# NeoCoreShield.net
KiCad netlist of a schematic drawn in EAGLE
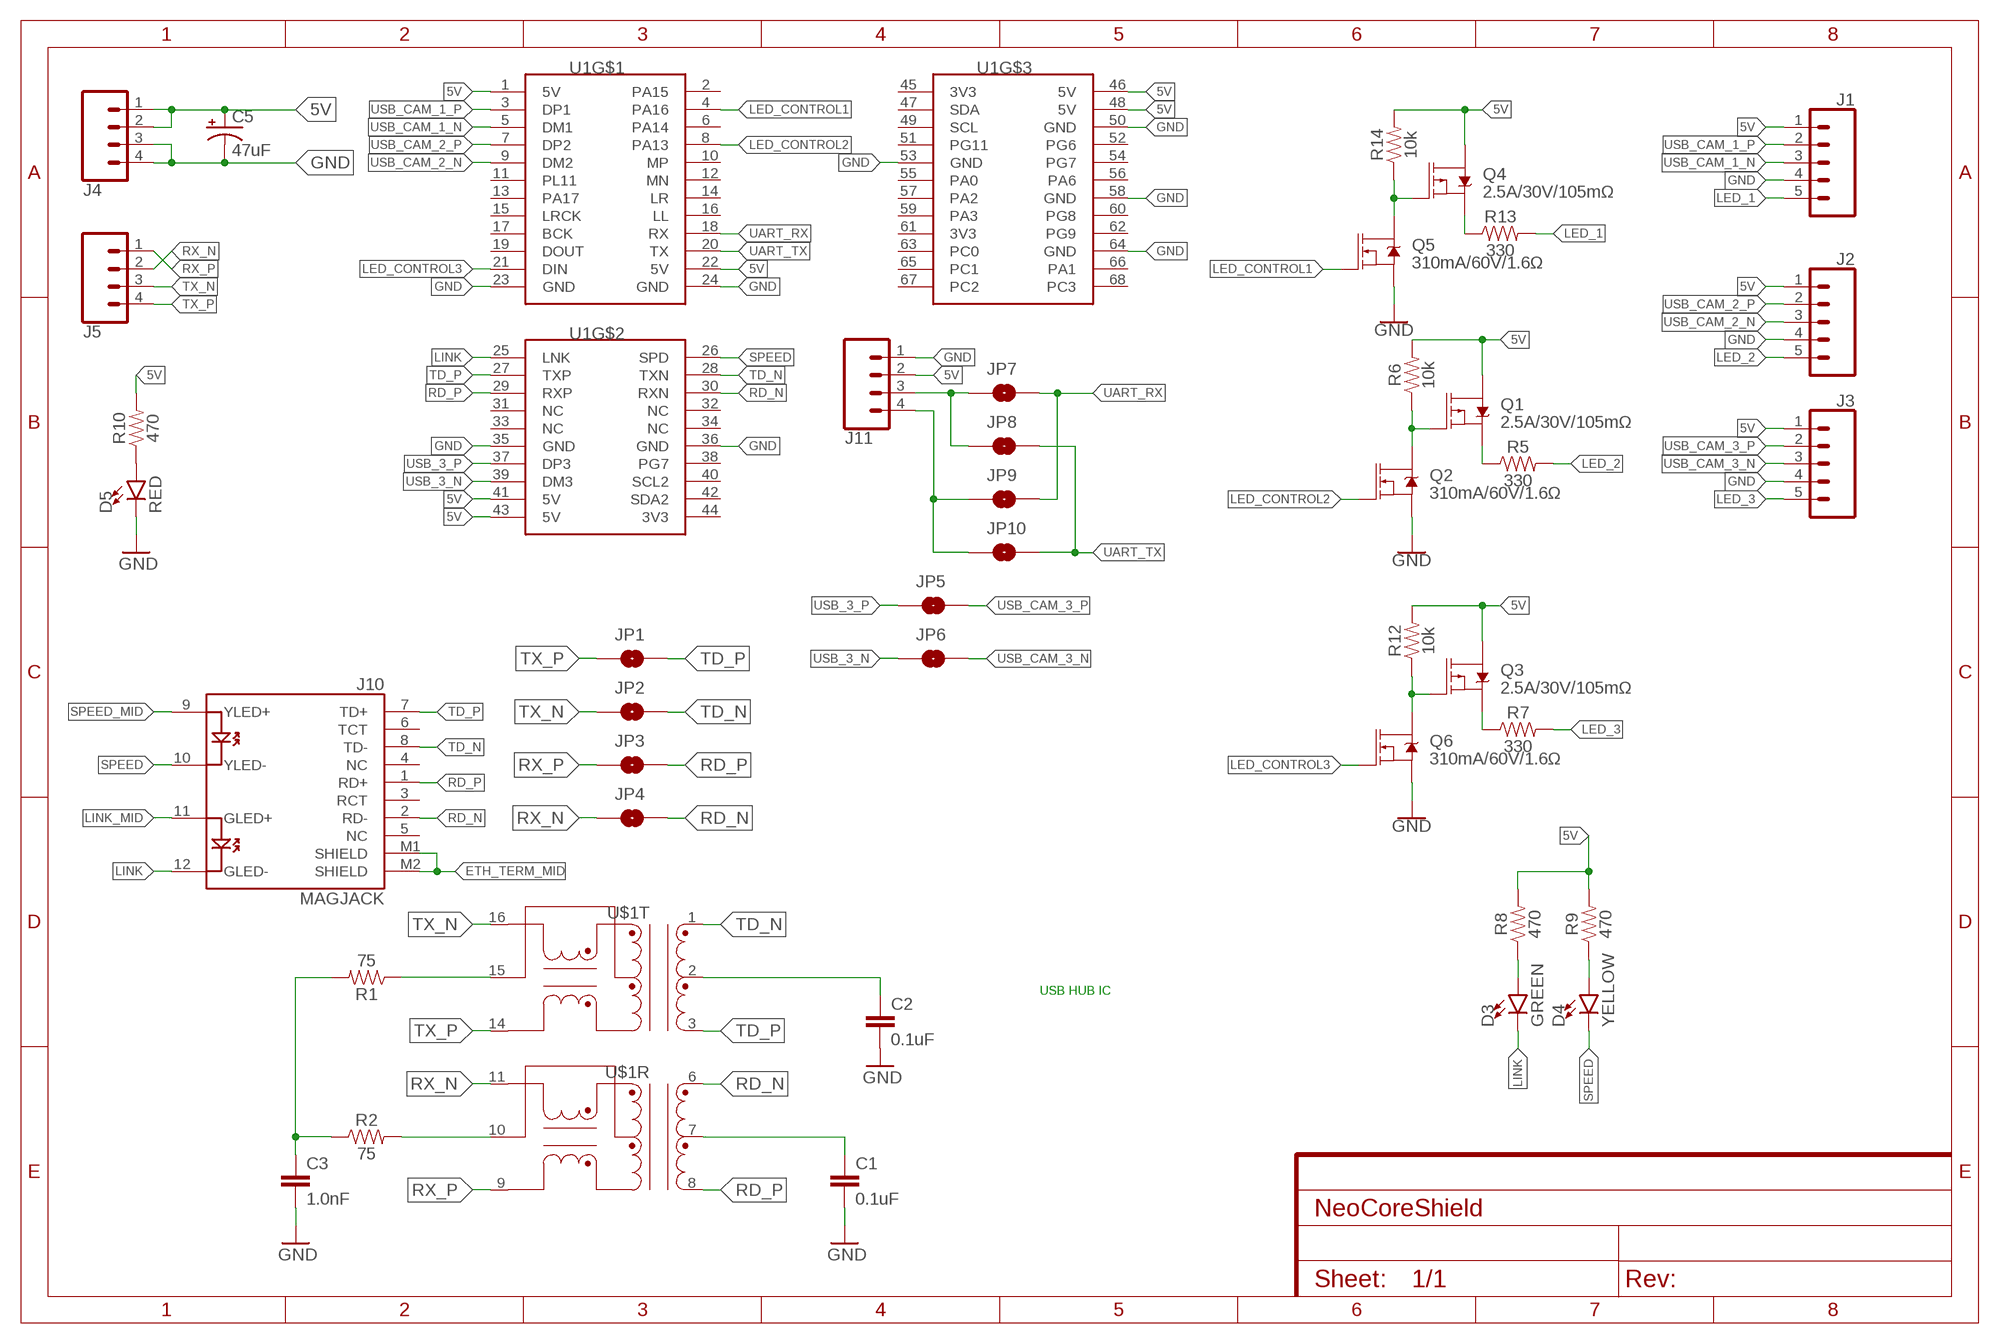
[diagram p0: schematic, sheet 1]

(export (version "E")
  (design (tool "Eeschema 10.0.6"))
  (components
    (comp (ref "C1")
      (value "0.1uF")
      (footprint "eagle-import:0603")
      (libsource (lib "eagle-import") (part "0.1UF-0603-25V-(+80/-20%)"))
    )
    (comp (ref "C2")
      (value "0.1uF")
      (footprint "eagle-import:0603")
      (libsource (lib "eagle-import") (part "0.1UF-0603-25V-(+80/-20%)"))
    )
    (comp (ref "C3")
      (value "1.0nF")
      (footprint "eagle-import:1206")
      (libsource (lib "eagle-import") (part "1.0UF-1206-50V-10%"))
    )
    (comp (ref "C5")
      (value "47uF")
      (footprint "eagle-import:PANASONIC_D")
      (libsource (lib "eagle-import") (part "47UF-POLAR-PANASONIC_D-35V-20%"))
    )
    (comp (ref "D3")
      (value "GREEN")
      (footprint "eagle-import:0805")
      (libsource (lib "eagle-import") (part "LED-0805"))
    )
    (comp (ref "D4")
      (value "YELLOW")
      (footprint "eagle-import:0805")
      (libsource (lib "eagle-import") (part "LED-0805"))
    )
    (comp (ref "D5")
      (value "RED")
      (footprint "eagle-import:0805")
      (libsource (lib "eagle-import") (part "LED-0805"))
    )
    (comp (ref "J1")
      (value "PXC-PTSM-05-RA")
      (footprint "eagle-import:PXC-PTSM-05-RA")
      (libsource (lib "eagle-import") (part "PXC-PTSM-05-RA"))
    )
    (comp (ref "J2")
      (value "PXC-PTSM-05-RA")
      (footprint "eagle-import:PXC-PTSM-05-RA")
      (libsource (lib "eagle-import") (part "PXC-PTSM-05-RA"))
    )
    (comp (ref "J3")
      (value "PXC-PTSM-05-RA")
      (footprint "eagle-import:PXC-PTSM-05-RA")
      (libsource (lib "eagle-import") (part "PXC-PTSM-05-RA"))
    )
    (comp (ref "J4")
      (value "PXC-PTSM-04-RA-1778641")
      (footprint "eagle-import:PXC-PTSM-04-RA-1778641")
      (libsource (lib "eagle-import") (part "PXC-PTSM-04-RA-1778641"))
    )
    (comp (ref "J5")
      (value "PXC-PTSM-04-RA-1778641")
      (footprint "eagle-import:PXC-PTSM-04-RA-1778641")
      (libsource (lib "eagle-import") (part "PXC-PTSM-04-RA-1778641"))
    )
    (comp (ref "J10")
      (value "MAGJACK")
      (footprint "eagle-import:MAGJACK")
      (libsource (lib "eagle-import") (part "MAGJACK"))
    )
    (comp (ref "J11")
      (value "CONN_04")
      (footprint "eagle-import:1X04")
      (libsource (lib "eagle-import") (part "CONN_04"))
    )
    (comp (ref "JP1")
      (value "JUMPER-SMT_2_NO_SILK")
      (footprint "eagle-import:SMT-JUMPER_2_NO_SILK")
      (libsource (lib "eagle-import") (part "JUMPER-SMT_2_NO_SILK"))
    )
    (comp (ref "JP2")
      (value "JUMPER-SMT_2_NO_SILK")
      (footprint "eagle-import:SMT-JUMPER_2_NO_SILK")
      (libsource (lib "eagle-import") (part "JUMPER-SMT_2_NO_SILK"))
    )
    (comp (ref "JP3")
      (value "JUMPER-SMT_2_NO_SILK")
      (footprint "eagle-import:SMT-JUMPER_2_NO_SILK")
      (libsource (lib "eagle-import") (part "JUMPER-SMT_2_NO_SILK"))
    )
    (comp (ref "JP4")
      (value "JUMPER-SMT_2_NO_SILK")
      (footprint "eagle-import:SMT-JUMPER_2_NO_SILK")
      (libsource (lib "eagle-import") (part "JUMPER-SMT_2_NO_SILK"))
    )
    (comp (ref "JP5")
      (value "JUMPER-SMT_2_NO_SILK")
      (footprint "eagle-import:SMT-JUMPER_2_NO_SILK")
      (libsource (lib "eagle-import") (part "JUMPER-SMT_2_NO_SILK"))
    )
    (comp (ref "JP6")
      (value "JUMPER-SMT_2_NO_SILK")
      (footprint "eagle-import:SMT-JUMPER_2_NO_SILK")
      (libsource (lib "eagle-import") (part "JUMPER-SMT_2_NO_SILK"))
    )
    (comp (ref "JP7")
      (value "JUMPER-SMT_2_NO_SILK")
      (footprint "eagle-import:SMT-JUMPER_2_NO_SILK")
      (libsource (lib "eagle-import") (part "JUMPER-SMT_2_NO_SILK"))
    )
    (comp (ref "JP8")
      (value "JUMPER-SMT_2_NO_SILK")
      (footprint "eagle-import:SMT-JUMPER_2_NO_SILK")
      (libsource (lib "eagle-import") (part "JUMPER-SMT_2_NO_SILK"))
    )
    (comp (ref "JP9")
      (value "JUMPER-SMT_2_NO_SILK")
      (footprint "eagle-import:SMT-JUMPER_2_NO_SILK")
      (libsource (lib "eagle-import") (part "JUMPER-SMT_2_NO_SILK"))
    )
    (comp (ref "JP10")
      (value "JUMPER-SMT_2_NO_SILK")
      (footprint "eagle-import:SMT-JUMPER_2_NO_SILK")
      (libsource (lib "eagle-import") (part "JUMPER-SMT_2_NO_SILK"))
    )
    (comp (ref "Q1")
      (value "2.5A/30V/105mΩ")
      (footprint "eagle-import:SOT23-3")
      (libsource (lib "eagle-import") (part "MOSFET_PCH-DMG2307L"))
    )
    (comp (ref "Q2")
      (value "310mA/60V/1.6Ω")
      (footprint "eagle-import:SOT323")
      (libsource (lib "eagle-import") (part "MOSFET-NCH-2N7002PW"))
    )
    (comp (ref "Q3")
      (value "2.5A/30V/105mΩ")
      (footprint "eagle-import:SOT23-3")
      (libsource (lib "eagle-import") (part "MOSFET_PCH-DMG2307L"))
    )
    (comp (ref "Q4")
      (value "2.5A/30V/105mΩ")
      (footprint "eagle-import:SOT23-3")
      (libsource (lib "eagle-import") (part "MOSFET_PCH-DMG2307L"))
    )
    (comp (ref "Q5")
      (value "310mA/60V/1.6Ω")
      (footprint "eagle-import:SOT323")
      (libsource (lib "eagle-import") (part "MOSFET-NCH-2N7002PW"))
    )
    (comp (ref "Q6")
      (value "310mA/60V/1.6Ω")
      (footprint "eagle-import:SOT323")
      (libsource (lib "eagle-import") (part "MOSFET-NCH-2N7002PW"))
    )
    (comp (ref "R1")
      (value "75")
      (footprint "eagle-import:0603")
      (libsource (lib "eagle-import") (part "75KOHM-0603-1/10W-1%"))
    )
    (comp (ref "R2")
      (value "75")
      (footprint "eagle-import:0603")
      (libsource (lib "eagle-import") (part "75KOHM-0603-1/10W-1%"))
    )
    (comp (ref "R5")
      (value "330")
      (footprint "eagle-import:0805")
      (libsource (lib "eagle-import") (part "RESISTOR0805"))
    )
    (comp (ref "R6")
      (value "10k")
      (footprint "eagle-import:0603")
      (libsource (lib "eagle-import") (part "10KOHM-0603-1/10W-1%"))
    )
    (comp (ref "R7")
      (value "330")
      (footprint "eagle-import:0805")
      (libsource (lib "eagle-import") (part "RESISTOR0805"))
    )
    (comp (ref "R8")
      (value "470")
      (footprint "eagle-import:0603")
      (libsource (lib "eagle-import") (part "0OHM-0603-1/10W-5%"))
    )
    (comp (ref "R9")
      (value "470")
      (footprint "eagle-import:0603")
      (libsource (lib "eagle-import") (part "0OHM-0603-1/10W-5%"))
    )
    (comp (ref "R10")
      (value "470")
      (footprint "eagle-import:0603")
      (libsource (lib "eagle-import") (part "0OHM-0603-1/10W-5%"))
    )
    (comp (ref "R12")
      (value "10k")
      (footprint "eagle-import:0603")
      (libsource (lib "eagle-import") (part "10KOHM-0603-1/10W-1%"))
    )
    (comp (ref "R13")
      (value "330")
      (footprint "eagle-import:0805")
      (libsource (lib "eagle-import") (part "RESISTOR0805"))
    )
    (comp (ref "R14")
      (value "10k")
      (footprint "eagle-import:0603")
      (libsource (lib "eagle-import") (part "10KOHM-0603-1/10W-1%"))
    )
    (comp (ref "U$1")
      (value "ETH-TRANS")
      (footprint "eagle-import:SOIC-16-WIDE")
      (libsource (lib "eagle-import") (part "ETH-TRANS"))
    )
    (comp (ref "U1")
      (value "NANO_PI_NEO_CORE")
      (footprint "eagle-import:NANO_PI_NEO_CORE")
      (libsource (lib "eagle-import") (part "NANO_PI_NEO_CORE"))
    )
  )
  (nets
    (net (code "1") (name "5V") (class "Default")
      (node (ref "C5") (pin "+") (pinfunction "+_+") (pintype "passive"))
      (node (ref "J1") (pin "1") (pinfunction "1_1") (pintype "passive"))
      (node (ref "J11") (pin "2") (pinfunction "2_2") (pintype "passive"))
      (node (ref "J2") (pin "1") (pinfunction "1_1") (pintype "passive"))
      (node (ref "J3") (pin "1") (pinfunction "1_1") (pintype "passive"))
      (node (ref "J4") (pin "1") (pinfunction "1_1") (pintype "passive"))
      (node (ref "J4") (pin "2") (pinfunction "2_2") (pintype "passive"))
      (node (ref "Q1") (pin "3") (pinfunction "D_3") (pintype "bidirectional"))
      (node (ref "Q3") (pin "3") (pinfunction "D_3") (pintype "bidirectional"))
      (node (ref "Q4") (pin "3") (pinfunction "D_3") (pintype "bidirectional"))
      (node (ref "R10") (pin "2") (pinfunction "2_2") (pintype "passive"))
      (node (ref "R12") (pin "2") (pinfunction "2_2") (pintype "passive"))
      (node (ref "R14") (pin "2") (pinfunction "2_2") (pintype "passive"))
      (node (ref "R6") (pin "2") (pinfunction "2_2") (pintype "passive"))
      (node (ref "R8") (pin "2") (pinfunction "2_2") (pintype "passive"))
      (node (ref "R9") (pin "2") (pinfunction "2_2") (pintype "passive"))
      (node (ref "U1") (pin "1") (pinfunction "5V_1") (pintype "bidirectional"))
      (node (ref "U1") (pin "22") (pinfunction "5V_22") (pintype "bidirectional"))
      (node (ref "U1") (pin "41") (pinfunction "5V_41") (pintype "bidirectional"))
      (node (ref "U1") (pin "43") (pinfunction "5V_43") (pintype "bidirectional"))
      (node (ref "U1") (pin "46") (pinfunction "5V_46") (pintype "bidirectional"))
      (node (ref "U1") (pin "48") (pinfunction "5V_48") (pintype "bidirectional"))
    )
    (net (code "2") (name "ETH_TERM_MID") (class "Default")
      (node (ref "C3") (pin "1") (pinfunction "1_1") (pintype "passive"))
      (node (ref "J10") (pin "M1") (pinfunction "SHIELD_M1") (pintype "bidirectional"))
      (node (ref "J10") (pin "M2") (pinfunction "SHIELD_M2") (pintype "bidirectional"))
      (node (ref "R1") (pin "2") (pinfunction "2_2") (pintype "passive"))
      (node (ref "R2") (pin "1") (pinfunction "1_1") (pintype "passive"))
    )
    (net (code "3") (name "GND") (class "Default")
      (node (ref "C1") (pin "2") (pinfunction "2_2") (pintype "passive"))
      (node (ref "C2") (pin "2") (pinfunction "2_2") (pintype "passive"))
      (node (ref "C3") (pin "2") (pinfunction "2_2") (pintype "passive"))
      (node (ref "C5") (pin "-") (pinfunction "-_-") (pintype "passive"))
      (node (ref "D5") (pin "C") (pinfunction "C_C") (pintype "passive"))
      (node (ref "J1") (pin "4") (pinfunction "4_4") (pintype "passive"))
      (node (ref "J11") (pin "1") (pinfunction "1_1") (pintype "passive"))
      (node (ref "J2") (pin "4") (pinfunction "4_4") (pintype "passive"))
      (node (ref "J3") (pin "4") (pinfunction "4_4") (pintype "passive"))
      (node (ref "J4") (pin "3") (pinfunction "3_3") (pintype "passive"))
      (node (ref "J4") (pin "4") (pinfunction "4_4") (pintype "passive"))
      (node (ref "Q2") (pin "2") (pinfunction "S_2") (pintype "bidirectional"))
      (node (ref "Q5") (pin "2") (pinfunction "S_2") (pintype "bidirectional"))
      (node (ref "Q6") (pin "2") (pinfunction "S_2") (pintype "bidirectional"))
      (node (ref "U1") (pin "23") (pinfunction "GND_23") (pintype "bidirectional"))
      (node (ref "U1") (pin "24") (pinfunction "GND_24") (pintype "bidirectional"))
      (node (ref "U1") (pin "35") (pinfunction "GND_35") (pintype "bidirectional"))
      (node (ref "U1") (pin "36") (pinfunction "GND_36") (pintype "bidirectional"))
      (node (ref "U1") (pin "50") (pinfunction "GND_50") (pintype "bidirectional"))
      (node (ref "U1") (pin "53") (pinfunction "GND_53") (pintype "bidirectional"))
      (node (ref "U1") (pin "58") (pinfunction "GND_58") (pintype "bidirectional"))
      (node (ref "U1") (pin "64") (pinfunction "GND_64") (pintype "bidirectional"))
    )
    (net (code "4") (name "LED_1") (class "Default")
      (node (ref "J1") (pin "5") (pinfunction "5_5") (pintype "passive"))
      (node (ref "R13") (pin "2") (pinfunction "2_2") (pintype "passive"))
    )
    (net (code "5") (name "LED_2") (class "Default")
      (node (ref "J2") (pin "5") (pinfunction "5_5") (pintype "passive"))
      (node (ref "R5") (pin "2") (pinfunction "2_2") (pintype "passive"))
    )
    (net (code "6") (name "LED_3") (class "Default")
      (node (ref "J3") (pin "5") (pinfunction "5_5") (pintype "passive"))
      (node (ref "R7") (pin "2") (pinfunction "2_2") (pintype "passive"))
    )
    (net (code "7") (name "LED_CONTROL1") (class "Default")
      (node (ref "Q5") (pin "1") (pinfunction "G_1") (pintype "bidirectional"))
      (node (ref "U1") (pin "4") (pinfunction "PA16_4") (pintype "bidirectional"))
    )
    (net (code "8") (name "LED_CONTROL2") (class "Default")
      (node (ref "Q2") (pin "1") (pinfunction "G_1") (pintype "bidirectional"))
      (node (ref "U1") (pin "8") (pinfunction "PA13_8") (pintype "bidirectional"))
    )
    (net (code "9") (name "LED_CONTROL3") (class "Default")
      (node (ref "Q6") (pin "1") (pinfunction "G_1") (pintype "bidirectional"))
      (node (ref "U1") (pin "21") (pinfunction "DIN_21") (pintype "bidirectional"))
    )
    (net (code "10") (name "LINK") (class "Default")
      (node (ref "D3") (pin "C") (pinfunction "C_C") (pintype "passive"))
      (node (ref "J10") (pin "12") (pinfunction "GLED-_12") (pintype "bidirectional"))
      (node (ref "U1") (pin "25") (pinfunction "LNK_25") (pintype "bidirectional"))
    )
    (net (code "11") (name "LINK_MID") (class "Default")
      (node (ref "D3") (pin "A") (pinfunction "A_A") (pintype "passive"))
      (node (ref "J10") (pin "11") (pinfunction "GLED+_11") (pintype "bidirectional"))
      (node (ref "R8") (pin "1") (pinfunction "1_1") (pintype "passive"))
    )
    (net (code "12") (name "Net-(D5-PadA)") (class "Default")
      (node (ref "D5") (pin "A") (pinfunction "A_A") (pintype "passive"))
      (node (ref "R10") (pin "1") (pinfunction "1_1") (pintype "passive"))
    )
    (net (code "13") (name "Net-(J11-Pad3)") (class "Default")
      (node (ref "J11") (pin "3") (pinfunction "3_3") (pintype "passive"))
      (node (ref "JP7") (pin "1") (pinfunction "1_1") (pintype "passive"))
      (node (ref "JP8") (pin "1") (pinfunction "1_1") (pintype "passive"))
    )
    (net (code "14") (name "Net-(J11-Pad4)") (class "Default")
      (node (ref "J11") (pin "4") (pinfunction "4_4") (pintype "passive"))
      (node (ref "JP10") (pin "1") (pinfunction "1_1") (pintype "passive"))
      (node (ref "JP9") (pin "1") (pinfunction "1_1") (pintype "passive"))
    )
    (net (code "15") (name "Net-(Q1-G)") (class "Default")
      (node (ref "Q1") (pin "1") (pinfunction "G_1") (pintype "bidirectional"))
      (node (ref "Q2") (pin "3") (pinfunction "D_3") (pintype "bidirectional"))
      (node (ref "R6") (pin "1") (pinfunction "1_1") (pintype "passive"))
    )
    (net (code "16") (name "Net-(Q1-S)") (class "Default")
      (node (ref "Q1") (pin "2") (pinfunction "S_2") (pintype "bidirectional"))
      (node (ref "R5") (pin "1") (pinfunction "1_1") (pintype "passive"))
    )
    (net (code "17") (name "Net-(Q3-G)") (class "Default")
      (node (ref "Q3") (pin "1") (pinfunction "G_1") (pintype "bidirectional"))
      (node (ref "Q6") (pin "3") (pinfunction "D_3") (pintype "bidirectional"))
      (node (ref "R12") (pin "1") (pinfunction "1_1") (pintype "passive"))
    )
    (net (code "18") (name "Net-(Q3-S)") (class "Default")
      (node (ref "Q3") (pin "2") (pinfunction "S_2") (pintype "bidirectional"))
      (node (ref "R7") (pin "1") (pinfunction "1_1") (pintype "passive"))
    )
    (net (code "19") (name "Net-(Q4-G)") (class "Default")
      (node (ref "Q4") (pin "1") (pinfunction "G_1") (pintype "bidirectional"))
      (node (ref "Q5") (pin "3") (pinfunction "D_3") (pintype "bidirectional"))
      (node (ref "R14") (pin "1") (pinfunction "1_1") (pintype "passive"))
    )
    (net (code "20") (name "Net-(Q4-S)") (class "Default")
      (node (ref "Q4") (pin "2") (pinfunction "S_2") (pintype "bidirectional"))
      (node (ref "R13") (pin "1") (pinfunction "1_1") (pintype "passive"))
    )
    (net (code "21") (name "Net-(U$1A-CT)") (class "Default")
      (node (ref "C1") (pin "1") (pinfunction "1_1") (pintype "passive"))
      (node (ref "U$1") (pin "7") (pinfunction "CT_7") (pintype "passive"))
    )
    (net (code "22") (name "Net-(U$1A-XCT)") (class "Default")
      (node (ref "R2") (pin "2") (pinfunction "2_2") (pintype "passive"))
      (node (ref "U$1") (pin "10") (pinfunction "XCT_10") (pintype "passive"))
    )
    (net (code "23") (name "Net-(U$1B-CT)") (class "Default")
      (node (ref "C2") (pin "1") (pinfunction "1_1") (pintype "passive"))
      (node (ref "U$1") (pin "2") (pinfunction "CT_2") (pintype "passive"))
    )
    (net (code "24") (name "Net-(U$1B-XCT)") (class "Default")
      (node (ref "R1") (pin "1") (pinfunction "1_1") (pintype "passive"))
      (node (ref "U$1") (pin "15") (pinfunction "XCT_15") (pintype "passive"))
    )
    (net (code "25") (name "RD_N") (class "Default")
      (node (ref "J10") (pin "2") (pinfunction "RD-_2") (pintype "bidirectional"))
      (node (ref "JP4") (pin "2") (pinfunction "2_2") (pintype "passive"))
      (node (ref "U$1") (pin "6") (pinfunction "D+_6") (pintype "passive"))
      (node (ref "U1") (pin "30") (pinfunction "RXN_30") (pintype "bidirectional"))
    )
    (net (code "26") (name "RD_P") (class "Default")
      (node (ref "J10") (pin "1") (pinfunction "RD+_1") (pintype "bidirectional"))
      (node (ref "JP3") (pin "2") (pinfunction "2_2") (pintype "passive"))
      (node (ref "U$1") (pin "8") (pinfunction "D-_8") (pintype "passive"))
      (node (ref "U1") (pin "29") (pinfunction "RXP_29") (pintype "bidirectional"))
    )
    (net (code "27") (name "RX_N") (class "Default")
      (node (ref "J5") (pin "2") (pinfunction "2_2") (pintype "passive"))
      (node (ref "JP4") (pin "1") (pinfunction "1_1") (pintype "passive"))
      (node (ref "U$1") (pin "11") (pinfunction "X+_11") (pintype "passive"))
    )
    (net (code "28") (name "RX_P") (class "Default")
      (node (ref "J5") (pin "1") (pinfunction "1_1") (pintype "passive"))
      (node (ref "JP3") (pin "1") (pinfunction "1_1") (pintype "passive"))
      (node (ref "U$1") (pin "9") (pinfunction "X-_9") (pintype "passive"))
    )
    (net (code "29") (name "SPEED") (class "Default")
      (node (ref "D4") (pin "C") (pinfunction "C_C") (pintype "passive"))
      (node (ref "J10") (pin "10") (pinfunction "YLED-_10") (pintype "bidirectional"))
      (node (ref "U1") (pin "26") (pinfunction "SPD_26") (pintype "bidirectional"))
    )
    (net (code "30") (name "SPEED_MID") (class "Default")
      (node (ref "D4") (pin "A") (pinfunction "A_A") (pintype "passive"))
      (node (ref "J10") (pin "9") (pinfunction "YLED+_9") (pintype "bidirectional"))
      (node (ref "R9") (pin "1") (pinfunction "1_1") (pintype "passive"))
    )
    (net (code "31") (name "TD_N") (class "Default")
      (node (ref "J10") (pin "8") (pinfunction "TD-_8") (pintype "bidirectional"))
      (node (ref "JP2") (pin "2") (pinfunction "2_2") (pintype "passive"))
      (node (ref "U$1") (pin "1") (pinfunction "D+_1") (pintype "passive"))
      (node (ref "U1") (pin "28") (pinfunction "TXN_28") (pintype "bidirectional"))
    )
    (net (code "32") (name "TD_P") (class "Default")
      (node (ref "J10") (pin "7") (pinfunction "TD+_7") (pintype "bidirectional"))
      (node (ref "JP1") (pin "2") (pinfunction "2_2") (pintype "passive"))
      (node (ref "U$1") (pin "3") (pinfunction "D-_3") (pintype "passive"))
      (node (ref "U1") (pin "27") (pinfunction "TXP_27") (pintype "bidirectional"))
    )
    (net (code "33") (name "TX_N") (class "Default")
      (node (ref "J5") (pin "3") (pinfunction "3_3") (pintype "passive"))
      (node (ref "JP2") (pin "1") (pinfunction "1_1") (pintype "passive"))
      (node (ref "U$1") (pin "16") (pinfunction "X+_16") (pintype "passive"))
    )
    (net (code "34") (name "TX_P") (class "Default")
      (node (ref "J5") (pin "4") (pinfunction "4_4") (pintype "passive"))
      (node (ref "JP1") (pin "1") (pinfunction "1_1") (pintype "passive"))
      (node (ref "U$1") (pin "14") (pinfunction "X-_14") (pintype "passive"))
    )
    (net (code "35") (name "UART_RX") (class "Default")
      (node (ref "JP7") (pin "2") (pinfunction "2_2") (pintype "passive"))
      (node (ref "JP9") (pin "2") (pinfunction "2_2") (pintype "passive"))
      (node (ref "U1") (pin "18") (pinfunction "RX_18") (pintype "bidirectional"))
    )
    (net (code "36") (name "UART_TX") (class "Default")
      (node (ref "JP10") (pin "2") (pinfunction "2_2") (pintype "passive"))
      (node (ref "JP8") (pin "2") (pinfunction "2_2") (pintype "passive"))
      (node (ref "U1") (pin "20") (pinfunction "TX_20") (pintype "bidirectional"))
    )
    (net (code "37") (name "USB_3_N") (class "Default")
      (node (ref "JP6") (pin "1") (pinfunction "1_1") (pintype "passive"))
      (node (ref "U1") (pin "39") (pinfunction "DM3_39") (pintype "bidirectional"))
    )
    (net (code "38") (name "USB_3_P") (class "Default")
      (node (ref "JP5") (pin "1") (pinfunction "1_1") (pintype "passive"))
      (node (ref "U1") (pin "37") (pinfunction "DP3_37") (pintype "bidirectional"))
    )
    (net (code "39") (name "USB_CAM_1_N") (class "Default")
      (node (ref "J1") (pin "3") (pinfunction "3_3") (pintype "passive"))
      (node (ref "U1") (pin "5") (pinfunction "DM1_5") (pintype "bidirectional"))
    )
    (net (code "40") (name "USB_CAM_1_P") (class "Default")
      (node (ref "J1") (pin "2") (pinfunction "2_2") (pintype "passive"))
      (node (ref "U1") (pin "3") (pinfunction "DP1_3") (pintype "bidirectional"))
    )
    (net (code "41") (name "USB_CAM_2_N") (class "Default")
      (node (ref "J2") (pin "3") (pinfunction "3_3") (pintype "passive"))
      (node (ref "U1") (pin "9") (pinfunction "DM2_9") (pintype "bidirectional"))
    )
    (net (code "42") (name "USB_CAM_2_P") (class "Default")
      (node (ref "J2") (pin "2") (pinfunction "2_2") (pintype "passive"))
      (node (ref "U1") (pin "7") (pinfunction "DP2_7") (pintype "bidirectional"))
    )
    (net (code "43") (name "USB_CAM_3_N") (class "Default")
      (node (ref "J3") (pin "3") (pinfunction "3_3") (pintype "passive"))
      (node (ref "JP6") (pin "2") (pinfunction "2_2") (pintype "passive"))
    )
    (net (code "44") (name "USB_CAM_3_P") (class "Default")
      (node (ref "J3") (pin "2") (pinfunction "2_2") (pintype "passive"))
      (node (ref "JP5") (pin "2") (pinfunction "2_2") (pintype "passive"))
    )
    (net (code "45") (name "unconnected-(J10-NC-Pad4)") (class "Default")
      (node (ref "J10") (pin "4") (pinfunction "NC_4") (pintype "bidirectional"))
    )
    (net (code "46") (name "unconnected-(J10-NC-Pad5)") (class "Default")
      (node (ref "J10") (pin "5") (pinfunction "NC_5") (pintype "bidirectional"))
    )
    (net (code "47") (name "unconnected-(J10-RCT-Pad3)") (class "Default")
      (node (ref "J10") (pin "3") (pinfunction "RCT_3") (pintype "bidirectional"))
    )
    (net (code "48") (name "unconnected-(J10-TCT-Pad6)") (class "Default")
      (node (ref "J10") (pin "6") (pinfunction "TCT_6") (pintype "bidirectional"))
    )
    (net (code "49") (name "unconnected-(U1A-BCK-Pad17)") (class "Default")
      (node (ref "U1") (pin "17") (pinfunction "BCK_17") (pintype "bidirectional"))
    )
    (net (code "50") (name "unconnected-(U1A-DOUT-Pad19)") (class "Default")
      (node (ref "U1") (pin "19") (pinfunction "DOUT_19") (pintype "bidirectional"))
    )
    (net (code "51") (name "unconnected-(U1A-LL-Pad16)") (class "Default")
      (node (ref "U1") (pin "16") (pinfunction "LL_16") (pintype "bidirectional"))
    )
    (net (code "52") (name "unconnected-(U1A-LR-Pad14)") (class "Default")
      (node (ref "U1") (pin "14") (pinfunction "LR_14") (pintype "bidirectional"))
    )
    (net (code "53") (name "unconnected-(U1A-LRCK-Pad15)") (class "Default")
      (node (ref "U1") (pin "15") (pinfunction "LRCK_15") (pintype "bidirectional"))
    )
    (net (code "54") (name "unconnected-(U1A-MN-Pad12)") (class "Default")
      (node (ref "U1") (pin "12") (pinfunction "MN_12") (pintype "bidirectional"))
    )
    (net (code "55") (name "unconnected-(U1A-MP-Pad10)") (class "Default")
      (node (ref "U1") (pin "10") (pinfunction "MP_10") (pintype "bidirectional"))
    )
    (net (code "56") (name "unconnected-(U1A-PA14-Pad6)") (class "Default")
      (node (ref "U1") (pin "6") (pinfunction "PA14_6") (pintype "bidirectional"))
    )
    (net (code "57") (name "unconnected-(U1A-PA15-Pad2)") (class "Default")
      (node (ref "U1") (pin "2") (pinfunction "PA15_2") (pintype "bidirectional"))
    )
    (net (code "58") (name "unconnected-(U1A-PA17-Pad13)") (class "Default")
      (node (ref "U1") (pin "13") (pinfunction "PA17_13") (pintype "bidirectional"))
    )
    (net (code "59") (name "unconnected-(U1A-PL11-Pad11)") (class "Default")
      (node (ref "U1") (pin "11") (pinfunction "PL11_11") (pintype "bidirectional"))
    )
    (net (code "60") (name "unconnected-(U1B-3V3-Pad44)") (class "Default")
      (node (ref "U1") (pin "44") (pinfunction "3V3_44") (pintype "bidirectional"))
    )
    (net (code "61") (name "unconnected-(U1B-NC-Pad31)") (class "Default")
      (node (ref "U1") (pin "31") (pinfunction "NC_31") (pintype "bidirectional"))
    )
    (net (code "62") (name "unconnected-(U1B-NC-Pad32)") (class "Default")
      (node (ref "U1") (pin "32") (pinfunction "NC_32") (pintype "bidirectional"))
    )
    (net (code "63") (name "unconnected-(U1B-NC-Pad33)") (class "Default")
      (node (ref "U1") (pin "33") (pinfunction "NC_33") (pintype "bidirectional"))
    )
    (net (code "64") (name "unconnected-(U1B-NC-Pad34)") (class "Default")
      (node (ref "U1") (pin "34") (pinfunction "NC_34") (pintype "bidirectional"))
    )
    (net (code "65") (name "unconnected-(U1B-PG7-Pad38)") (class "Default")
      (node (ref "U1") (pin "38") (pinfunction "PG7_38") (pintype "bidirectional"))
    )
    (net (code "66") (name "unconnected-(U1B-SCL2-Pad40)") (class "Default")
      (node (ref "U1") (pin "40") (pinfunction "SCL2_40") (pintype "bidirectional"))
    )
    (net (code "67") (name "unconnected-(U1B-SDA2-Pad42)") (class "Default")
      (node (ref "U1") (pin "42") (pinfunction "SDA2_42") (pintype "bidirectional"))
    )
    (net (code "68") (name "unconnected-(U1C-3V3-Pad45)") (class "Default")
      (node (ref "U1") (pin "45") (pinfunction "3V3_45") (pintype "bidirectional"))
    )
    (net (code "69") (name "unconnected-(U1C-3V3-Pad61)") (class "Default")
      (node (ref "U1") (pin "61") (pinfunction "3V3_61") (pintype "bidirectional"))
    )
    (net (code "70") (name "unconnected-(U1C-PA0-Pad55)") (class "Default")
      (node (ref "U1") (pin "55") (pinfunction "PA0_55") (pintype "bidirectional"))
    )
    (net (code "71") (name "unconnected-(U1C-PA1-Pad66)") (class "Default")
      (node (ref "U1") (pin "66") (pinfunction "PA1_66") (pintype "bidirectional"))
    )
    (net (code "72") (name "unconnected-(U1C-PA2-Pad57)") (class "Default")
      (node (ref "U1") (pin "57") (pinfunction "PA2_57") (pintype "bidirectional"))
    )
    (net (code "73") (name "unconnected-(U1C-PA3-Pad59)") (class "Default")
      (node (ref "U1") (pin "59") (pinfunction "PA3_59") (pintype "bidirectional"))
    )
    (net (code "74") (name "unconnected-(U1C-PA6-Pad56)") (class "Default")
      (node (ref "U1") (pin "56") (pinfunction "PA6_56") (pintype "bidirectional"))
    )
    (net (code "75") (name "unconnected-(U1C-PC0-Pad63)") (class "Default")
      (node (ref "U1") (pin "63") (pinfunction "PC0_63") (pintype "bidirectional"))
    )
    (net (code "76") (name "unconnected-(U1C-PC1-Pad65)") (class "Default")
      (node (ref "U1") (pin "65") (pinfunction "PC1_65") (pintype "bidirectional"))
    )
    (net (code "77") (name "unconnected-(U1C-PC2-Pad67)") (class "Default")
      (node (ref "U1") (pin "67") (pinfunction "PC2_67") (pintype "bidirectional"))
    )
    (net (code "78") (name "unconnected-(U1C-PC3-Pad68)") (class "Default")
      (node (ref "U1") (pin "68") (pinfunction "PC3_68") (pintype "bidirectional"))
    )
    (net (code "79") (name "unconnected-(U1C-PG6-Pad52)") (class "Default")
      (node (ref "U1") (pin "52") (pinfunction "PG6_52") (pintype "bidirectional"))
    )
    (net (code "80") (name "unconnected-(U1C-PG7-Pad54)") (class "Default")
      (node (ref "U1") (pin "54") (pinfunction "PG7_54") (pintype "bidirectional"))
    )
    (net (code "81") (name "unconnected-(U1C-PG8-Pad60)") (class "Default")
      (node (ref "U1") (pin "60") (pinfunction "PG8_60") (pintype "bidirectional"))
    )
    (net (code "82") (name "unconnected-(U1C-PG9-Pad62)") (class "Default")
      (node (ref "U1") (pin "62") (pinfunction "PG9_62") (pintype "bidirectional"))
    )
    (net (code "83") (name "unconnected-(U1C-PG11-Pad51)") (class "Default")
      (node (ref "U1") (pin "51") (pinfunction "PG11_51") (pintype "bidirectional"))
    )
    (net (code "84") (name "unconnected-(U1C-SCL-Pad49)") (class "Default")
      (node (ref "U1") (pin "49") (pinfunction "SCL_49") (pintype "bidirectional"))
    )
    (net (code "85") (name "unconnected-(U1C-SDA-Pad47)") (class "Default")
      (node (ref "U1") (pin "47") (pinfunction "SDA_47") (pintype "bidirectional"))
    )
  )
)
